# MAX931.net
KiCad netlist of a schematic drawn in Altium Designer
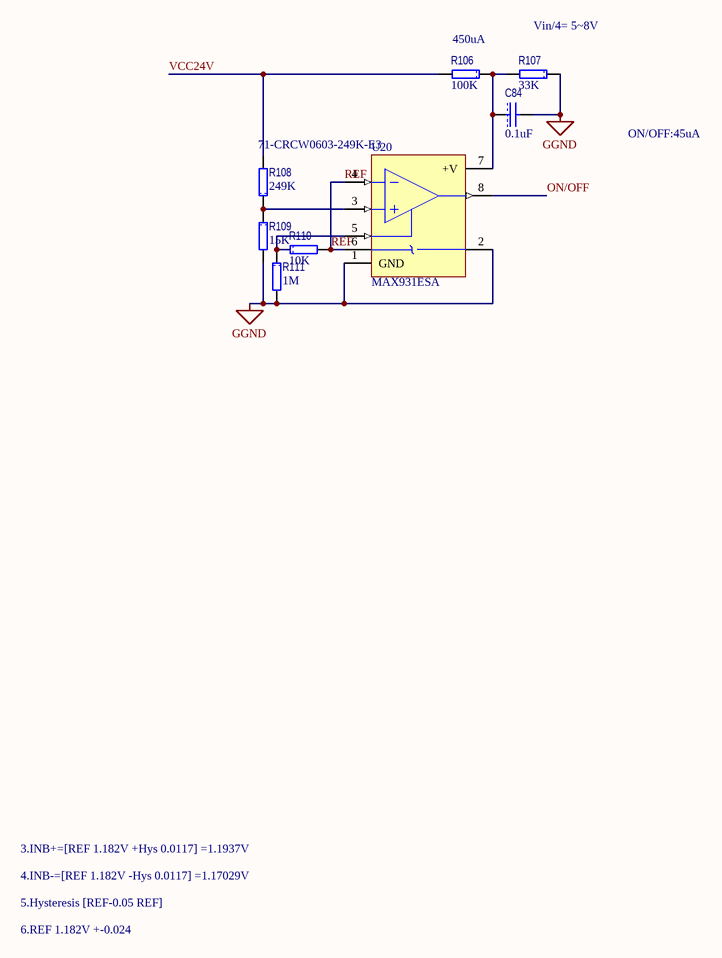
[diagram p0: 低电压关断_MAX931.SchDoc]

(export (version "E")
  (design (tool "Eeschema 10.0.6"))
  (components
    (comp (ref "C84")
      (value "0.1uF")
      (footprint "1608[0603]C")
      (description "多层陶瓷电容器MLCC - SMD/SMT 0603 0.1uF 50volts X7R 10%")
      (fields (field (name "MANUFACTURER") "TDK") (field (name "MANUFACTURER PART NUMBER") "C1608X7R1H104K"))
      (libsource (lib "*") (part "CAP"))
    )
    (comp (ref "R106")
      (value "100K")
      (footprint "1608[0603]R")
      (description "厚膜电阻器 - SMD 1/10watt 200Kohms 1%")
      (fields (field (name "Comment") "CRCW0603100KFKEA"))
      (libsource (lib "10K 1%") (part "RES"))
    )
    (comp (ref "R107")
      (value "33K")
      (footprint "1608[0603]R")
      (description "厚膜电阻器 - SMD 1/10watt 33Kohms 1%")
      (fields (field (name "Comment") "CRCW060333K0FKEA"))
      (libsource (lib "10K 1%") (part "RES"))
    )
    (comp (ref "R108")
      (value "249K")
      (footprint "1608[0603]R")
      (description "厚膜电阻器 - SMD 1/10watt 249Kohms 1%")
      (fields
        (field (name "SUPPLIER PART NUMBER 1") "71-CRCW0603-249K-E3")
        (field (name "MANUFACTURER") "Vishay / Dale")
        (field (name "MANUFACTURER PART NUMBER") "CRCW0603249KFKEA")
      )
      (libsource (lib "10K 1%") (part "RES"))
    )
    (comp (ref "R109")
      (value "15K")
      (footprint "1608[0603]R")
      (description "厚膜电阻器 - SMD 1/10watt 15Kohms 1%")
      (fields
        (field (name "MANUFACTURER") "Vishay / Dale")
        (field (name "MANUFACTURER PART NUMBER") "CRCW060315K0FKEA")
      )
      (libsource (lib "10K 1%") (part "RES"))
    )
    (comp (ref "R110")
      (value "10K")
      (footprint "1608[0603]R")
      (description "厚膜电阻器 - SMD 1/10watt 10Kohms 1%")
      (fields
        (field (name "MANUFACTURER") "Vishay / Dale")
        (field (name "MANUFACTURER PART NUMBER") "CRCW060310K0FKEA")
      )
      (libsource (lib "10K 1%") (part "RES"))
    )
    (comp (ref "R111")
      (value "1M")
      (footprint "1608[0603]R")
      (description "厚膜电阻器 - SMD 1/10watt 10Kohms 1%")
      (fields
        (field (name "MANUFACTURER") "Vishay / Dale")
        (field (name "MANUFACTURER PART NUMBER") "CRCW060310K0FKEA")
      )
      (libsource (lib "10K 1%") (part "RES"))
    )
    (comp (ref "U20")
      (value "MAX931ESA")
      (footprint "NSO8_N")
      (description "Ultra Low-Power, Low-Cost Comparator with 2% Reference")
      (fields (field (name "PUBLISHER") "Altium Limited"))
      (libsource (lib "Maxim Analog Comparator") (part "MAX931ESA"))
    )
  )
  (nets
    (net (code "1") (name "/ON{slash}OFF") (class "Default")
      (node (ref "U20") (pin "8") (pinfunction "OUT_8") (pintype "output"))
    )
    (net (code "2") (name "/REF") (class "Default")
      (node (ref "R110") (pin "2") (pinfunction "2_2") (pintype "passive"))
      (node (ref "U20") (pin "4") (pinfunction "IN-_4") (pintype "input"))
      (node (ref "U20") (pin "6") (pinfunction "REF_6") (pintype "passive"))
    )
    (net (code "3") (name "/VCC24V") (class "Default")
      (node (ref "R106") (pin "2") (pinfunction "2_2") (pintype "passive"))
      (node (ref "R108") (pin "2") (pinfunction "2_2") (pintype "passive"))
    )
    (net (code "4") (name "GGND") (class "Default")
      (node (ref "C84") (pin "2") (pinfunction "2_2") (pintype "passive"))
      (node (ref "R107") (pin "1") (pinfunction "1_1") (pintype "passive"))
      (node (ref "R109") (pin "2") (pinfunction "2_2") (pintype "passive"))
      (node (ref "R111") (pin "2") (pinfunction "2_2") (pintype "passive"))
      (node (ref "U20") (pin "1") (pinfunction "GND_1") (pintype "power_in"))
      (node (ref "U20") (pin "2") (pinfunction "-V_2") (pintype "power_in"))
    )
    (net (code "5") (name "Net-(U20-+V)") (class "Default")
      (node (ref "C84") (pin "1") (pinfunction "1_1") (pintype "passive"))
      (node (ref "R106") (pin "1") (pinfunction "1_1") (pintype "passive"))
      (node (ref "R107") (pin "2") (pinfunction "2_2") (pintype "passive"))
      (node (ref "U20") (pin "7") (pinfunction "+V_7") (pintype "power_in"))
    )
    (net (code "6") (name "Net-(U20-HYST)") (class "Default")
      (node (ref "R110") (pin "1") (pinfunction "1_1") (pintype "passive"))
      (node (ref "R111") (pin "1") (pinfunction "1_1") (pintype "passive"))
      (node (ref "U20") (pin "5") (pinfunction "HYST_5") (pintype "input"))
    )
    (net (code "7") (name "Net-(U20-IN+)") (class "Default")
      (node (ref "R108") (pin "1") (pinfunction "1_1") (pintype "passive"))
      (node (ref "R109") (pin "1") (pinfunction "1_1") (pintype "passive"))
      (node (ref "U20") (pin "3") (pinfunction "IN+_3") (pintype "input"))
    )
  )
)
